# IR_Line8.net
KiCad netlist of a schematic drawn in EAGLE
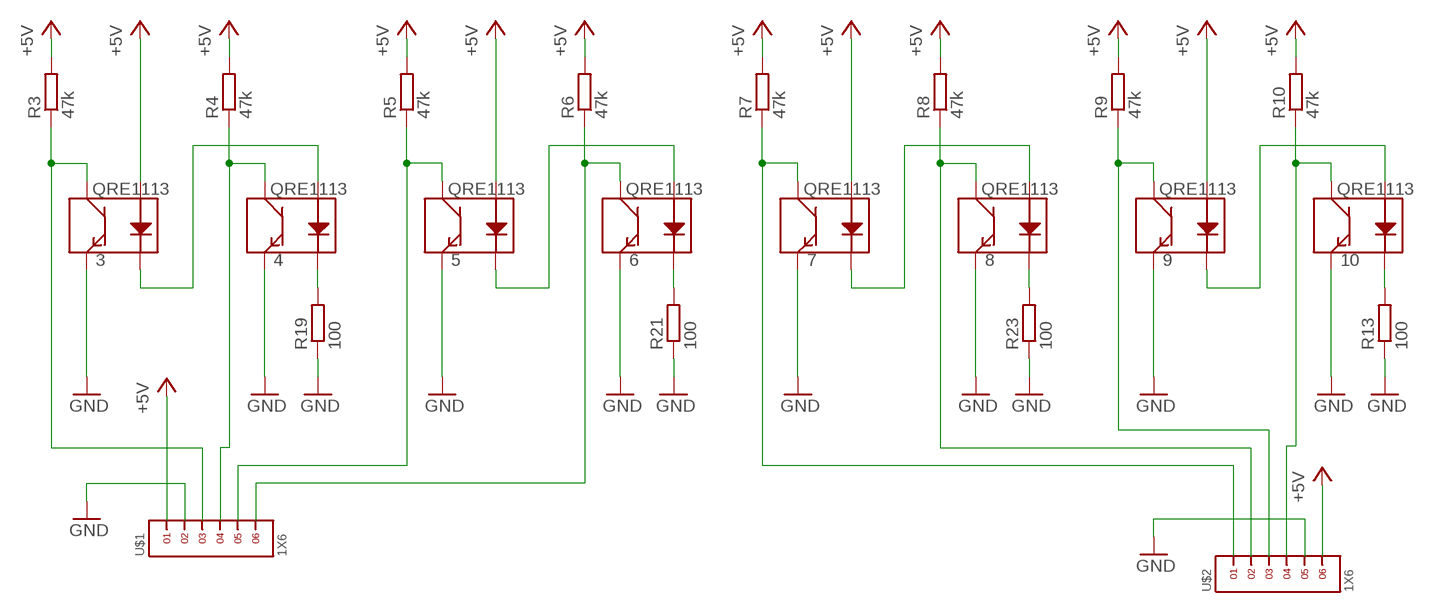
[diagram p0: schematic, sheet 1]

(export (version "E")
  (design (tool "Eeschema 10.0.6"))
  (components
    (comp (ref "3")
      (value "QRE1113")
      (footprint "eagle-import:QRE1113")
      (libsource (lib "eagle-import") (part "QRE1113"))
    )
    (comp (ref "4")
      (value "QRE1113")
      (footprint "eagle-import:QRE1113")
      (libsource (lib "eagle-import") (part "QRE1113"))
    )
    (comp (ref "5")
      (value "QRE1113")
      (footprint "eagle-import:QRE1113")
      (libsource (lib "eagle-import") (part "QRE1113"))
    )
    (comp (ref "6")
      (value "QRE1113")
      (footprint "eagle-import:QRE1113")
      (libsource (lib "eagle-import") (part "QRE1113"))
    )
    (comp (ref "7")
      (value "QRE1113")
      (footprint "eagle-import:QRE1113")
      (libsource (lib "eagle-import") (part "QRE1113"))
    )
    (comp (ref "8")
      (value "QRE1113")
      (footprint "eagle-import:QRE1113")
      (libsource (lib "eagle-import") (part "QRE1113"))
    )
    (comp (ref "9")
      (value "QRE1113")
      (footprint "eagle-import:QRE1113")
      (libsource (lib "eagle-import") (part "QRE1113"))
    )
    (comp (ref "10")
      (value "QRE1113")
      (footprint "eagle-import:QRE1113")
      (libsource (lib "eagle-import") (part "QRE1113"))
    )
    (comp (ref "R3")
      (value "47k")
      (footprint "eagle-import:R0805")
      (libsource (lib "eagle-import") (part "R-EU_R0805"))
    )
    (comp (ref "R4")
      (value "47k")
      (footprint "eagle-import:R0805")
      (libsource (lib "eagle-import") (part "R-EU_R0805"))
    )
    (comp (ref "R5")
      (value "47k")
      (footprint "eagle-import:R0805")
      (libsource (lib "eagle-import") (part "R-EU_R0805"))
    )
    (comp (ref "R6")
      (value "47k")
      (footprint "eagle-import:R0805")
      (libsource (lib "eagle-import") (part "R-EU_R0805"))
    )
    (comp (ref "R7")
      (value "47k")
      (footprint "eagle-import:R0805")
      (libsource (lib "eagle-import") (part "R-EU_R0805"))
    )
    (comp (ref "R8")
      (value "47k")
      (footprint "eagle-import:R0805")
      (libsource (lib "eagle-import") (part "R-EU_R0805"))
    )
    (comp (ref "R9")
      (value "47k")
      (footprint "eagle-import:R0805")
      (libsource (lib "eagle-import") (part "R-EU_R0805"))
    )
    (comp (ref "R10")
      (value "47k")
      (footprint "eagle-import:R0805")
      (libsource (lib "eagle-import") (part "R-EU_R0805"))
    )
    (comp (ref "R13")
      (value "100")
      (footprint "eagle-import:R0805")
      (libsource (lib "eagle-import") (part "R-EU_R0805"))
    )
    (comp (ref "R19")
      (value "100")
      (footprint "eagle-import:R0805")
      (libsource (lib "eagle-import") (part "R-EU_R0805"))
    )
    (comp (ref "R21")
      (value "100")
      (footprint "eagle-import:R0805")
      (libsource (lib "eagle-import") (part "R-EU_R0805"))
    )
    (comp (ref "R23")
      (value "100")
      (footprint "eagle-import:R0805")
      (libsource (lib "eagle-import") (part "R-EU_R0805"))
    )
    (comp (ref "U$1")
      (value "1X6")
      (footprint "eagle-import:1X6")
      (libsource (lib "eagle-import") (part "1X6"))
    )
    (comp (ref "U$2")
      (value "1X6")
      (footprint "eagle-import:1X6")
      (libsource (lib "eagle-import") (part "1X6"))
    )
  )
  (nets
    (net (code "1") (name "+5V") (class "Default")
      (node (ref "3") (pin "1") (pinfunction "A_1") (pintype "bidirectional"))
      (node (ref "5") (pin "1") (pinfunction "A_1") (pintype "bidirectional"))
      (node (ref "7") (pin "1") (pinfunction "A_1") (pintype "bidirectional"))
      (node (ref "9") (pin "1") (pinfunction "A_1") (pintype "bidirectional"))
      (node (ref "R10") (pin "2") (pinfunction "2_2") (pintype "passive"))
      (node (ref "R3") (pin "2") (pinfunction "2_2") (pintype "passive"))
      (node (ref "R4") (pin "2") (pinfunction "2_2") (pintype "passive"))
      (node (ref "R5") (pin "2") (pinfunction "2_2") (pintype "passive"))
      (node (ref "R6") (pin "2") (pinfunction "2_2") (pintype "passive"))
      (node (ref "R7") (pin "2") (pinfunction "2_2") (pintype "passive"))
      (node (ref "R8") (pin "2") (pinfunction "2_2") (pintype "passive"))
      (node (ref "R9") (pin "2") (pinfunction "2_2") (pintype "passive"))
      (node (ref "U$1") (pin "1") (pinfunction "1_1") (pintype "bidirectional"))
      (node (ref "U$2") (pin "6") (pinfunction "6_6") (pintype "bidirectional"))
    )
    (net (code "2") (name "GND") (class "Default")
      (node (ref "10") (pin "4") (pinfunction "E_4") (pintype "bidirectional"))
      (node (ref "3") (pin "4") (pinfunction "E_4") (pintype "bidirectional"))
      (node (ref "4") (pin "4") (pinfunction "E_4") (pintype "bidirectional"))
      (node (ref "5") (pin "4") (pinfunction "E_4") (pintype "bidirectional"))
      (node (ref "6") (pin "4") (pinfunction "E_4") (pintype "bidirectional"))
      (node (ref "7") (pin "4") (pinfunction "E_4") (pintype "bidirectional"))
      (node (ref "8") (pin "4") (pinfunction "E_4") (pintype "bidirectional"))
      (node (ref "9") (pin "4") (pinfunction "E_4") (pintype "bidirectional"))
      (node (ref "R13") (pin "1") (pinfunction "1_1") (pintype "passive"))
      (node (ref "R19") (pin "1") (pinfunction "1_1") (pintype "passive"))
      (node (ref "R21") (pin "1") (pinfunction "1_1") (pintype "passive"))
      (node (ref "R23") (pin "1") (pinfunction "1_1") (pintype "passive"))
      (node (ref "U$1") (pin "2") (pinfunction "2_2") (pintype "bidirectional"))
      (node (ref "U$2") (pin "5") (pinfunction "5_5") (pintype "bidirectional"))
    )
    (net (code "3") (name "Net-(3-C)") (class "Default")
      (node (ref "3") (pin "3") (pinfunction "C_3") (pintype "bidirectional"))
      (node (ref "R3") (pin "1") (pinfunction "1_1") (pintype "passive"))
      (node (ref "U$1") (pin "3") (pinfunction "3_3") (pintype "bidirectional"))
    )
    (net (code "4") (name "Net-(3-K)") (class "Default")
      (node (ref "3") (pin "2") (pinfunction "K_2") (pintype "bidirectional"))
      (node (ref "4") (pin "1") (pinfunction "A_1") (pintype "bidirectional"))
    )
    (net (code "5") (name "Net-(4-C)") (class "Default")
      (node (ref "4") (pin "3") (pinfunction "C_3") (pintype "bidirectional"))
      (node (ref "R4") (pin "1") (pinfunction "1_1") (pintype "passive"))
      (node (ref "U$1") (pin "4") (pinfunction "4_4") (pintype "bidirectional"))
    )
    (net (code "6") (name "Net-(4-K)") (class "Default")
      (node (ref "4") (pin "2") (pinfunction "K_2") (pintype "bidirectional"))
      (node (ref "R19") (pin "2") (pinfunction "2_2") (pintype "passive"))
    )
    (net (code "7") (name "Net-(5-C)") (class "Default")
      (node (ref "5") (pin "3") (pinfunction "C_3") (pintype "bidirectional"))
      (node (ref "R5") (pin "1") (pinfunction "1_1") (pintype "passive"))
      (node (ref "U$1") (pin "5") (pinfunction "5_5") (pintype "bidirectional"))
    )
    (net (code "8") (name "Net-(5-K)") (class "Default")
      (node (ref "5") (pin "2") (pinfunction "K_2") (pintype "bidirectional"))
      (node (ref "6") (pin "1") (pinfunction "A_1") (pintype "bidirectional"))
    )
    (net (code "9") (name "Net-(6-C)") (class "Default")
      (node (ref "6") (pin "3") (pinfunction "C_3") (pintype "bidirectional"))
      (node (ref "R6") (pin "1") (pinfunction "1_1") (pintype "passive"))
      (node (ref "U$1") (pin "6") (pinfunction "6_6") (pintype "bidirectional"))
    )
    (net (code "10") (name "Net-(6-K)") (class "Default")
      (node (ref "6") (pin "2") (pinfunction "K_2") (pintype "bidirectional"))
      (node (ref "R21") (pin "2") (pinfunction "2_2") (pintype "passive"))
    )
    (net (code "11") (name "Net-(7-C)") (class "Default")
      (node (ref "7") (pin "3") (pinfunction "C_3") (pintype "bidirectional"))
      (node (ref "R7") (pin "1") (pinfunction "1_1") (pintype "passive"))
      (node (ref "U$2") (pin "1") (pinfunction "1_1") (pintype "bidirectional"))
    )
    (net (code "12") (name "Net-(7-K)") (class "Default")
      (node (ref "7") (pin "2") (pinfunction "K_2") (pintype "bidirectional"))
      (node (ref "8") (pin "1") (pinfunction "A_1") (pintype "bidirectional"))
    )
    (net (code "13") (name "Net-(8-C)") (class "Default")
      (node (ref "8") (pin "3") (pinfunction "C_3") (pintype "bidirectional"))
      (node (ref "R8") (pin "1") (pinfunction "1_1") (pintype "passive"))
      (node (ref "U$2") (pin "2") (pinfunction "2_2") (pintype "bidirectional"))
    )
    (net (code "14") (name "Net-(8-K)") (class "Default")
      (node (ref "8") (pin "2") (pinfunction "K_2") (pintype "bidirectional"))
      (node (ref "R23") (pin "2") (pinfunction "2_2") (pintype "passive"))
    )
    (net (code "15") (name "Net-(9-C)") (class "Default")
      (node (ref "9") (pin "3") (pinfunction "C_3") (pintype "bidirectional"))
      (node (ref "R9") (pin "1") (pinfunction "1_1") (pintype "passive"))
      (node (ref "U$2") (pin "3") (pinfunction "3_3") (pintype "bidirectional"))
    )
    (net (code "16") (name "Net-(10-A)") (class "Default")
      (node (ref "10") (pin "1") (pinfunction "A_1") (pintype "bidirectional"))
      (node (ref "9") (pin "2") (pinfunction "K_2") (pintype "bidirectional"))
    )
    (net (code "17") (name "Net-(10-C)") (class "Default")
      (node (ref "10") (pin "3") (pinfunction "C_3") (pintype "bidirectional"))
      (node (ref "R10") (pin "1") (pinfunction "1_1") (pintype "passive"))
      (node (ref "U$2") (pin "4") (pinfunction "4_4") (pintype "bidirectional"))
    )
    (net (code "18") (name "Net-(10-K)") (class "Default")
      (node (ref "10") (pin "2") (pinfunction "K_2") (pintype "bidirectional"))
      (node (ref "R13") (pin "2") (pinfunction "2_2") (pintype "passive"))
    )
  )
)
